# regelschaltplan_e7.net
KiCad netlist of a schematic drawn in EAGLE
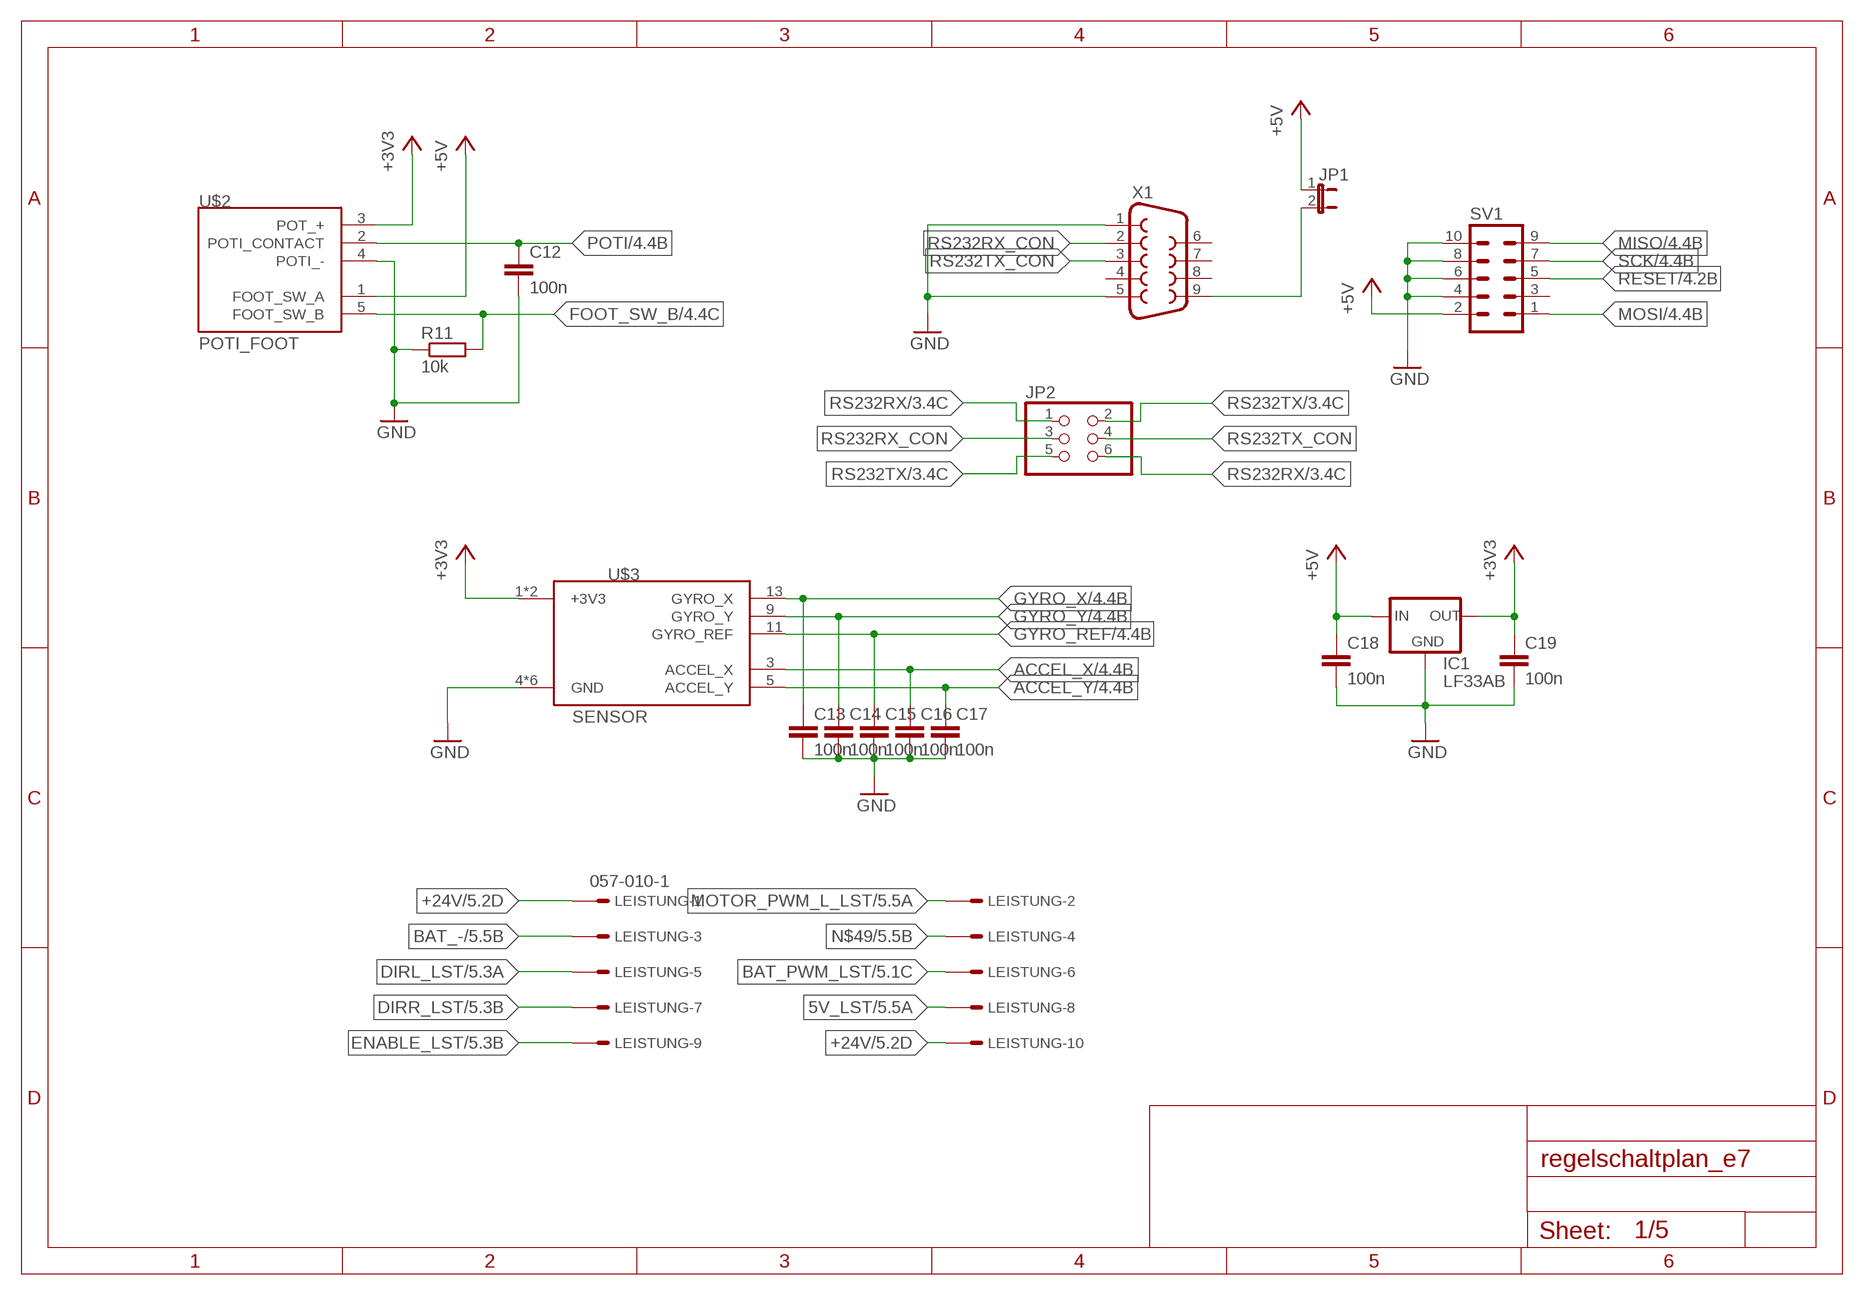
[diagram p0: schematic, sheet 1]
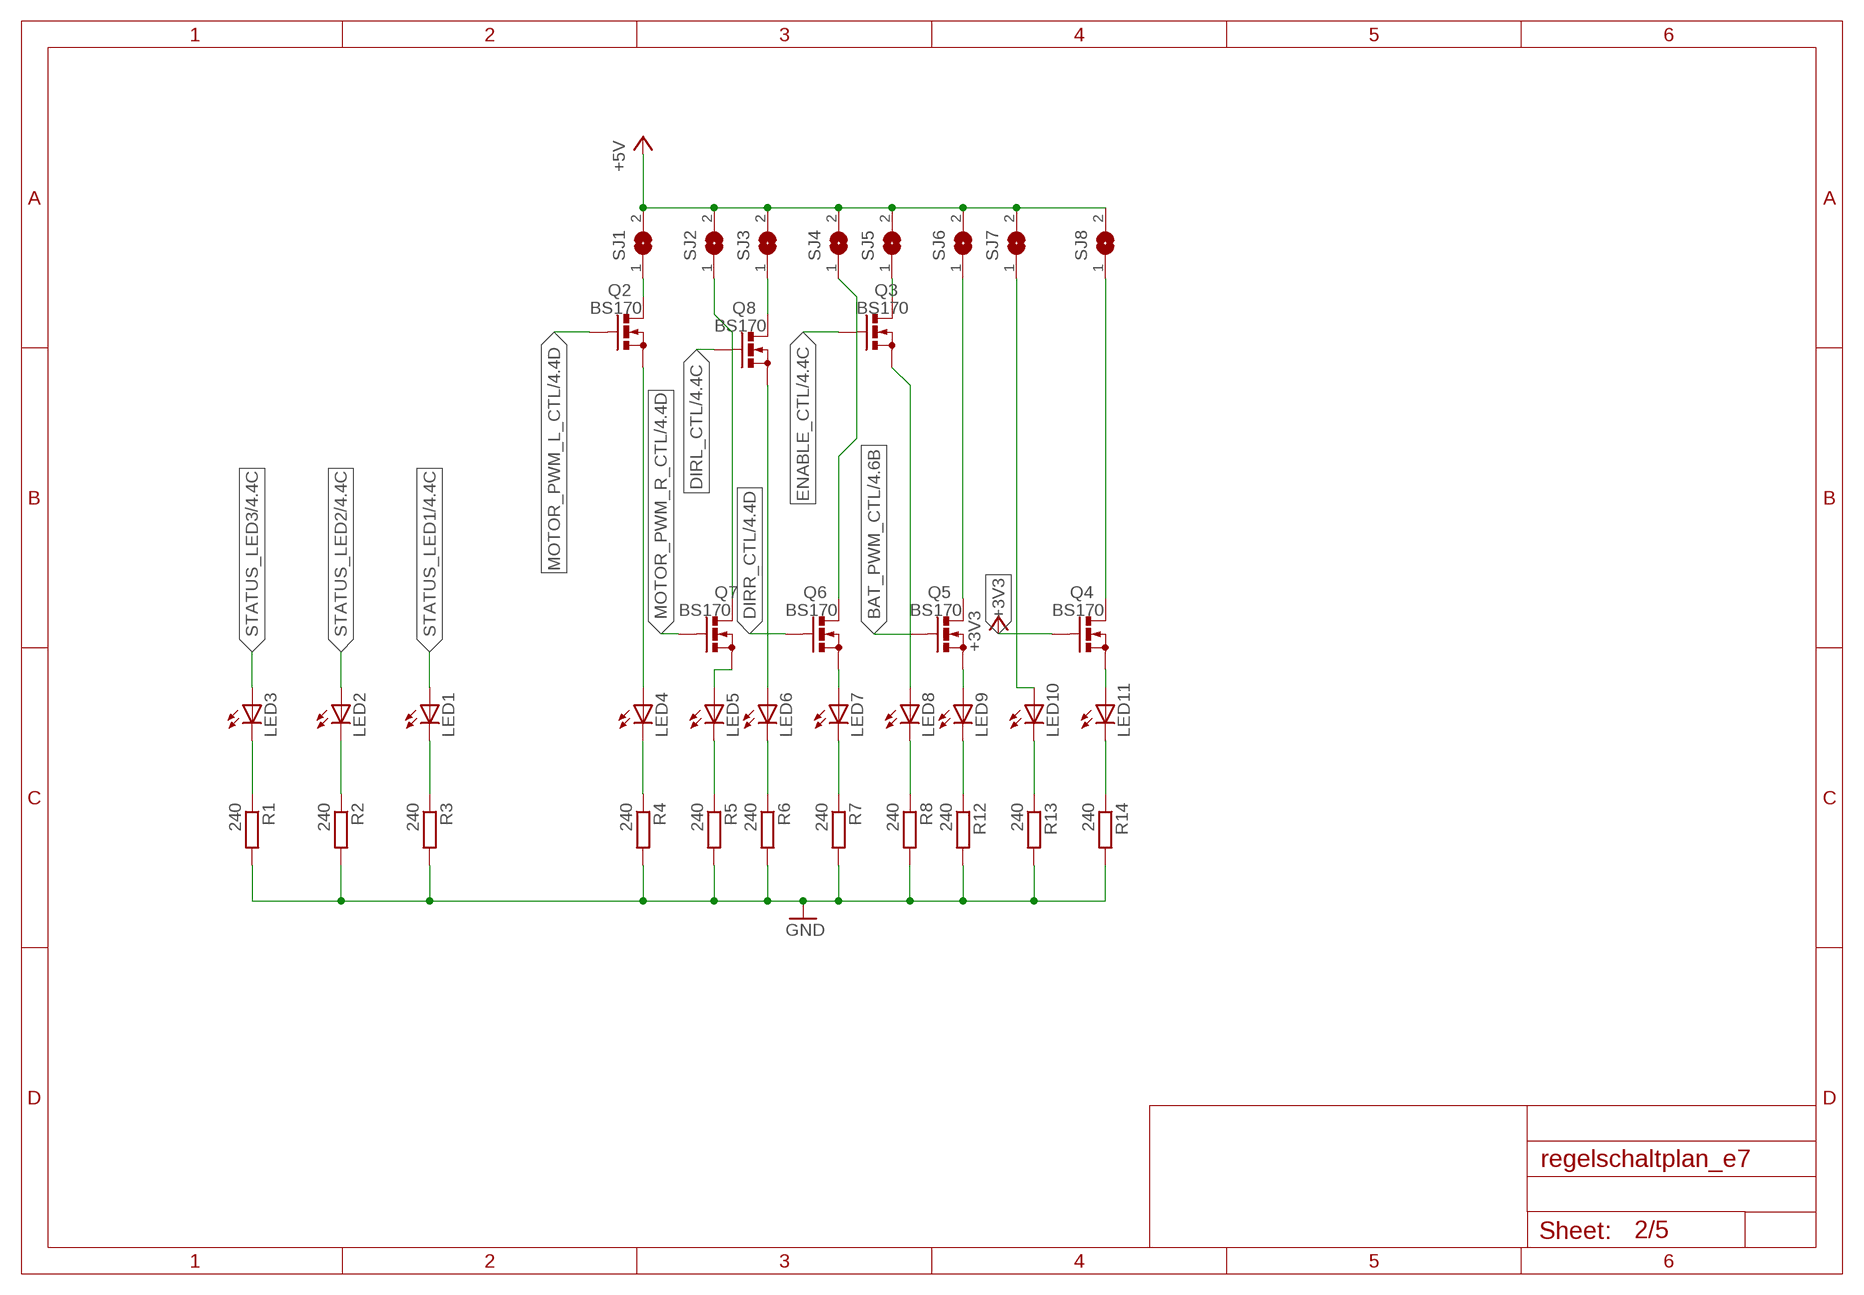
[diagram p1: schematic, sheet 2]
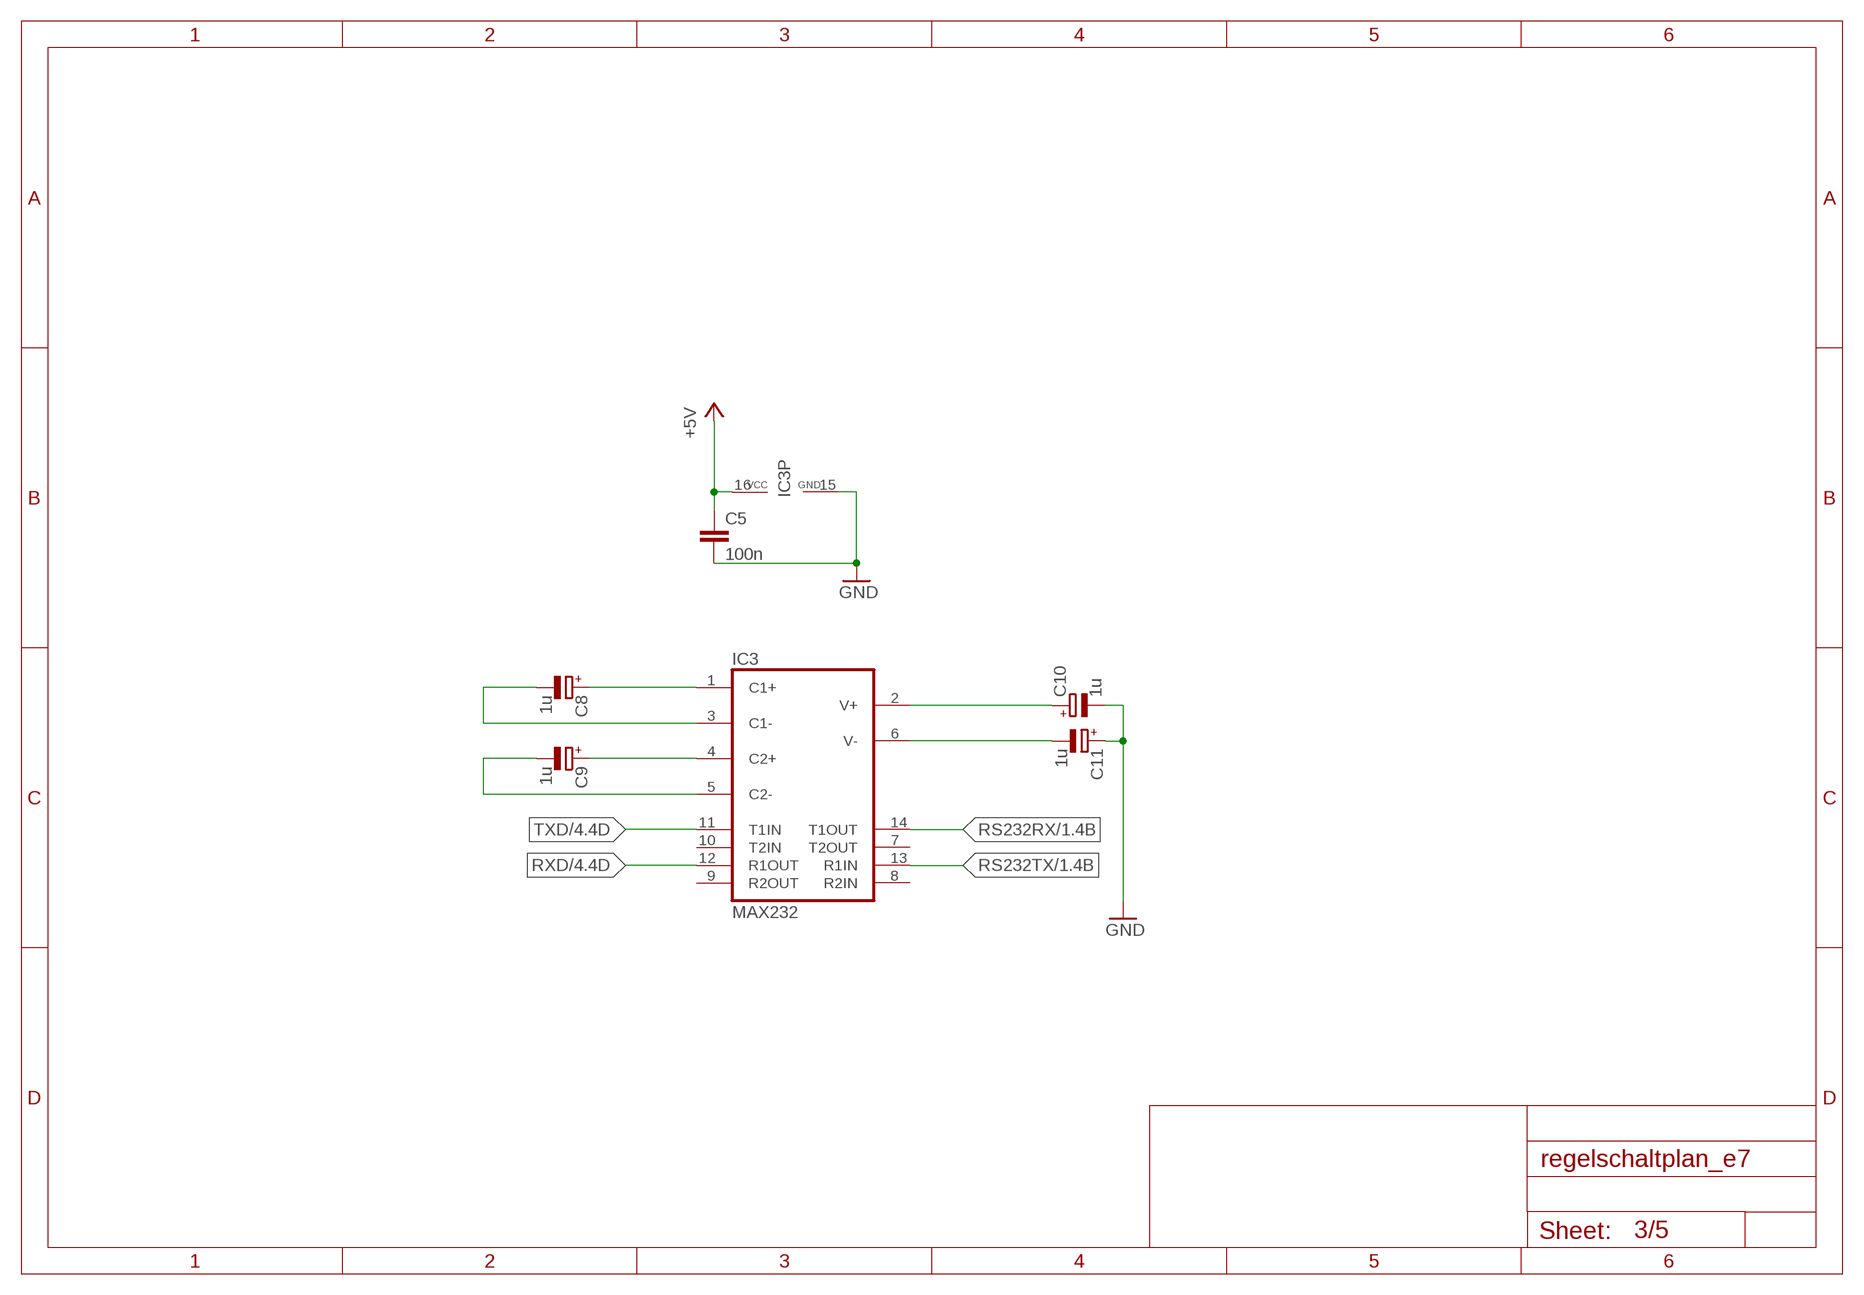
[diagram p2: schematic, sheet 3]
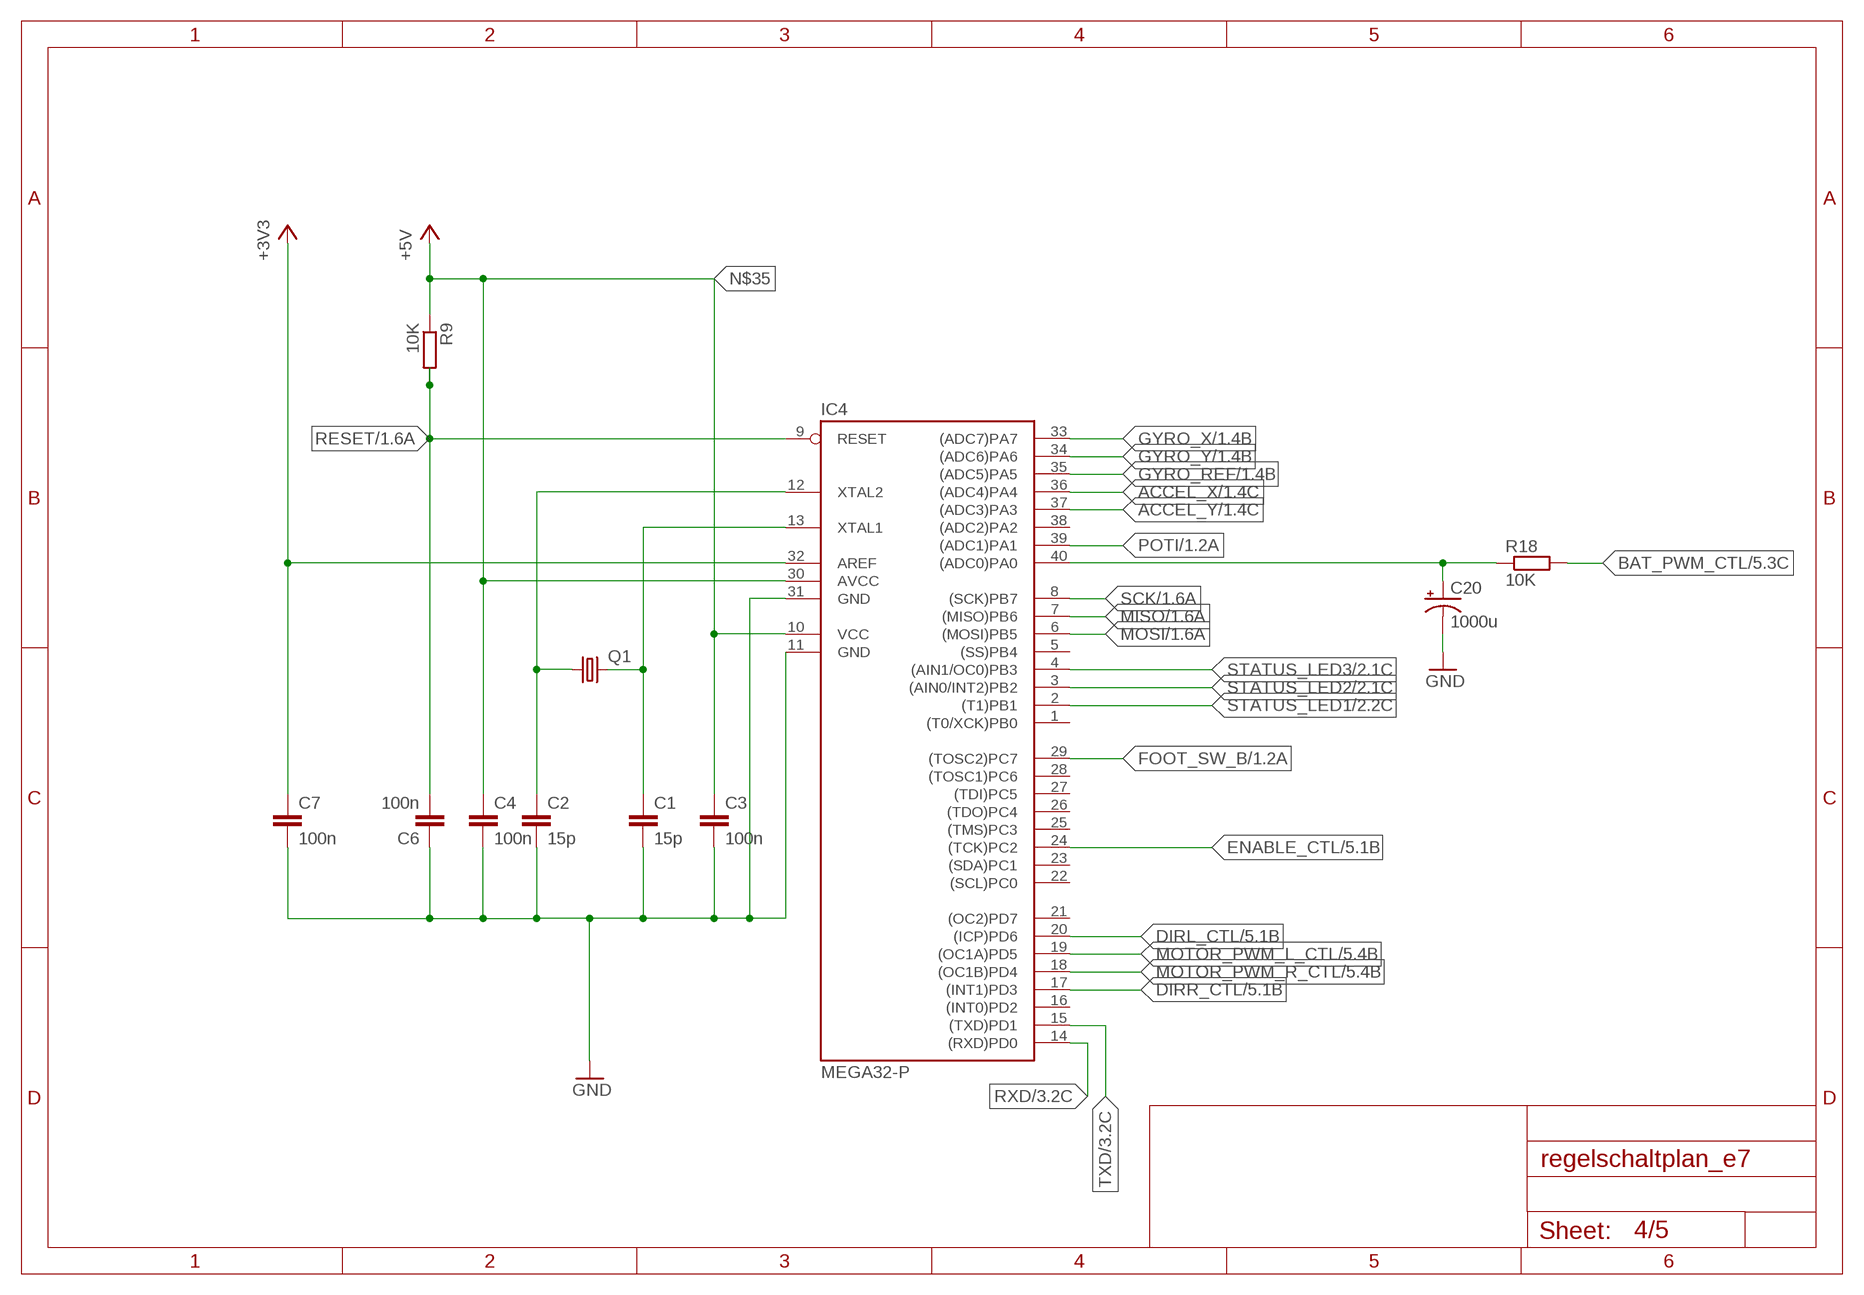
[diagram p3: schematic, sheet 4]
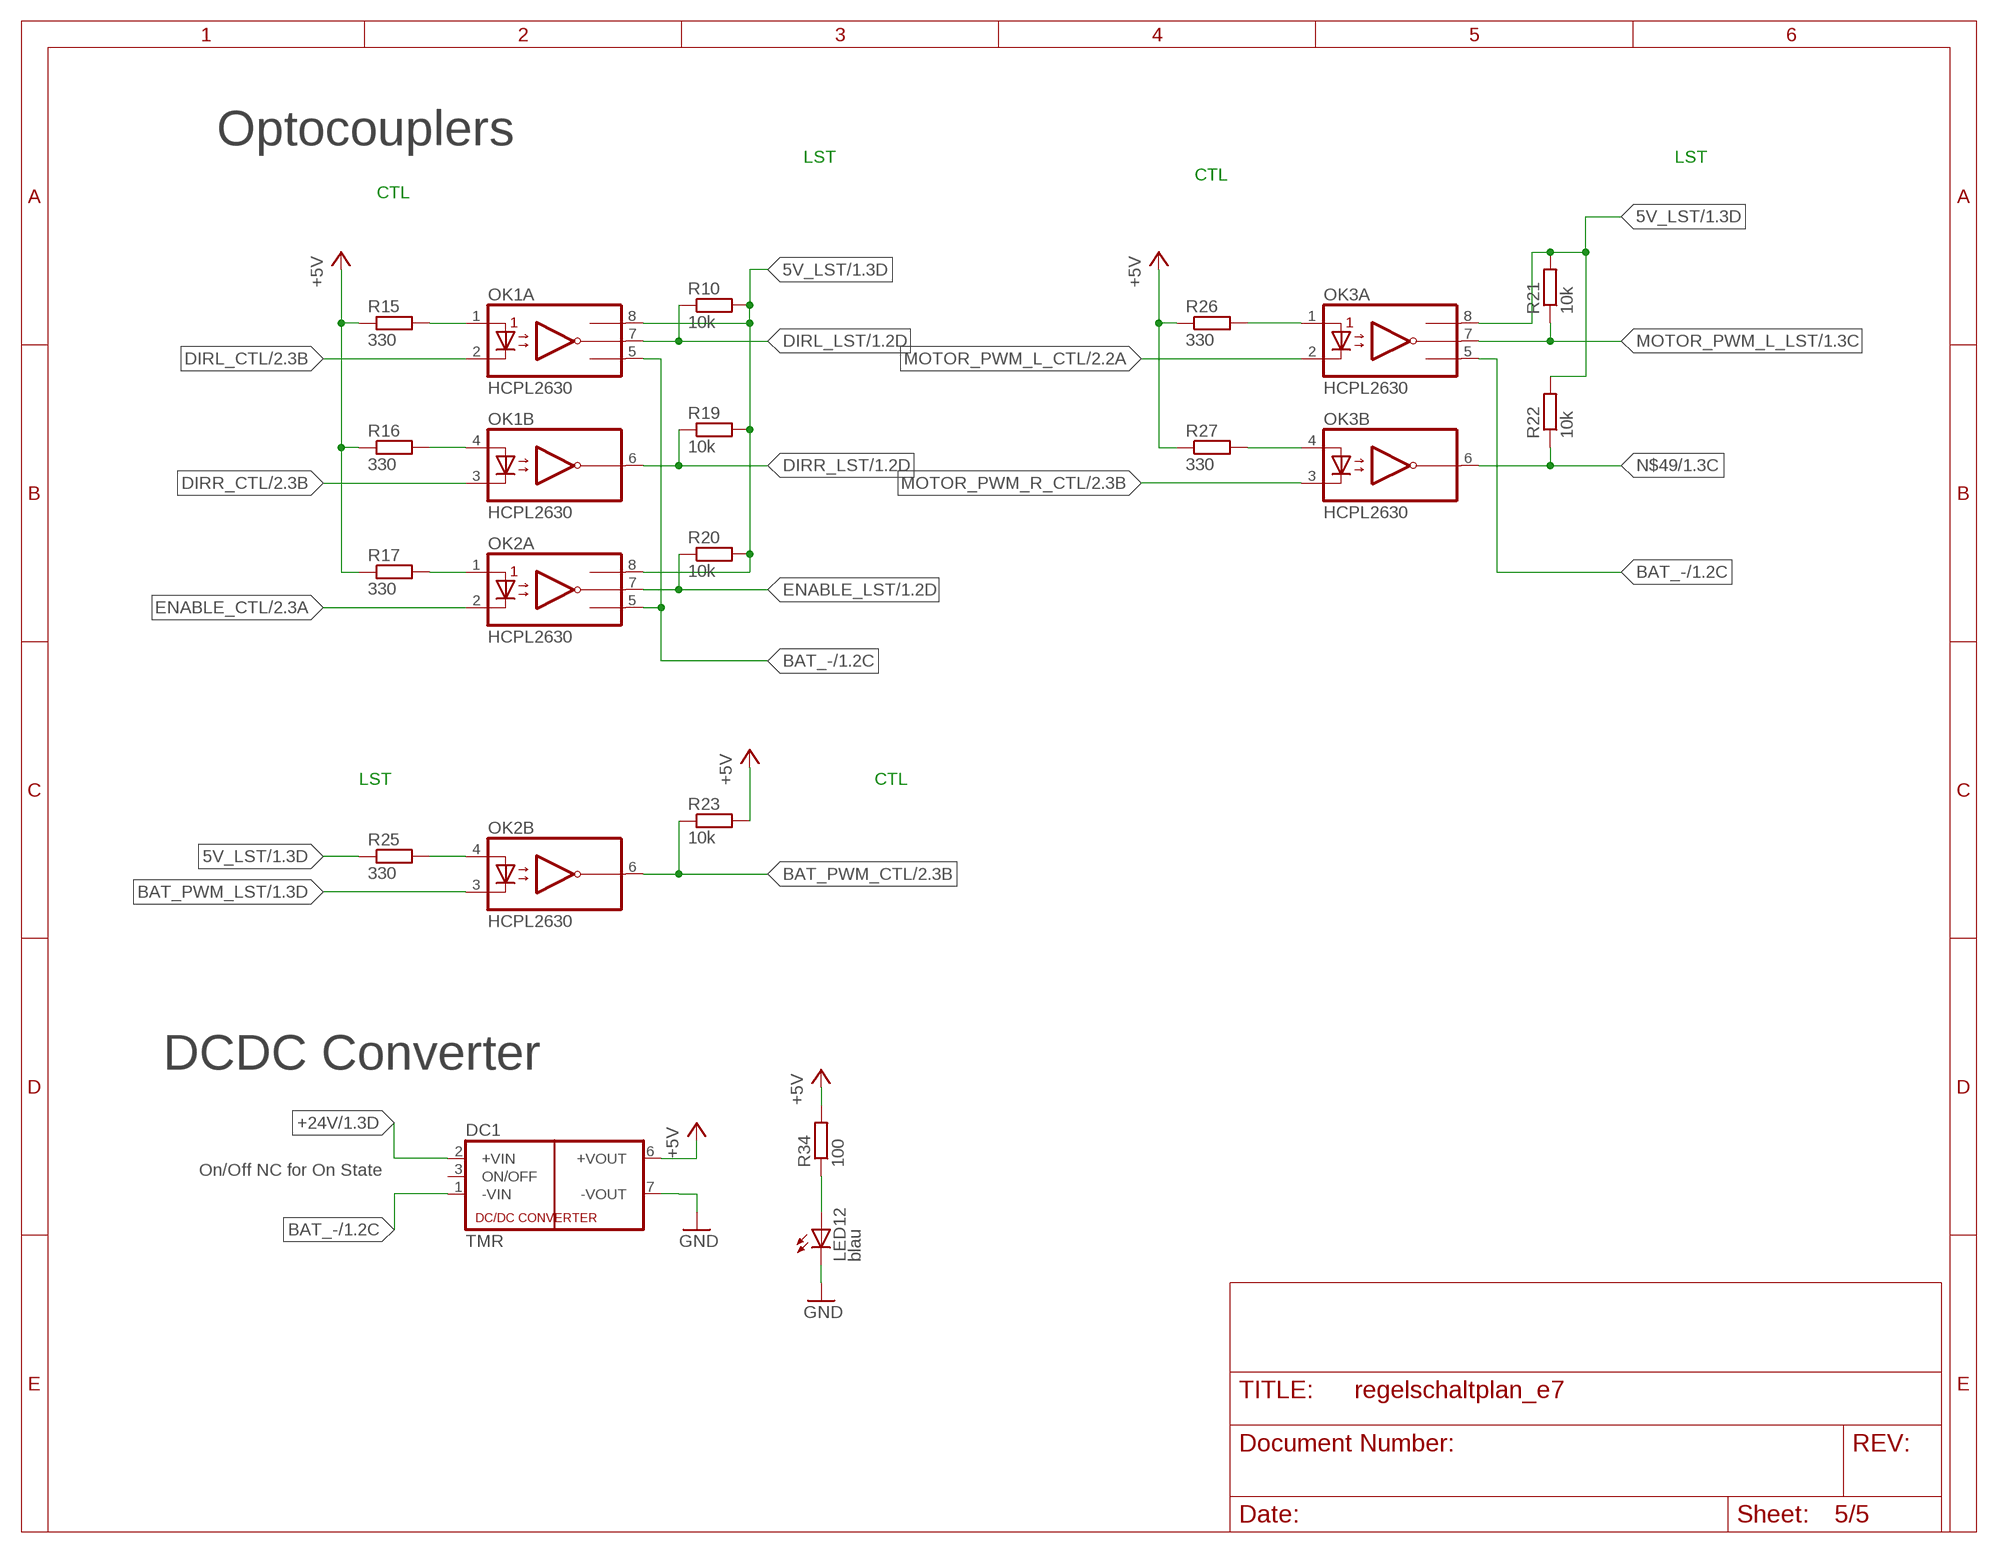
[diagram p4: schematic, sheet 5]

(export (version "E")
  (design (tool "Eeschema 10.0.6"))
  (components
    (comp (ref "C12")
      (value "100n")
      (footprint "eagle-import:C025-025X050")
      (libsource (lib "eagle-import") (part "C-EU025-025X050"))
    )
    (comp (ref "C13")
      (value "100n")
      (footprint "eagle-import:C025-025X050")
      (libsource (lib "eagle-import") (part "C-EU025-025X050"))
    )
    (comp (ref "C14")
      (value "100n")
      (footprint "eagle-import:C025-025X050")
      (libsource (lib "eagle-import") (part "C-EU025-025X050"))
    )
    (comp (ref "C15")
      (value "100n")
      (footprint "eagle-import:C025-025X050")
      (libsource (lib "eagle-import") (part "C-EU025-025X050"))
    )
    (comp (ref "C16")
      (value "100n")
      (footprint "eagle-import:C025-025X050")
      (libsource (lib "eagle-import") (part "C-EU025-025X050"))
    )
    (comp (ref "C17")
      (value "100n")
      (footprint "eagle-import:C025-025X050")
      (libsource (lib "eagle-import") (part "C-EU025-025X050"))
    )
    (comp (ref "C18")
      (value "100n")
      (footprint "eagle-import:C025-025X050")
      (libsource (lib "eagle-import") (part "C-EU025-025X050"))
    )
    (comp (ref "C19")
      (value "100n")
      (footprint "eagle-import:C025-025X050")
      (libsource (lib "eagle-import") (part "C-EU025-025X050"))
    )
    (comp (ref "IC1")
      (value "LF33AB")
      (footprint "eagle-import:TO220")
      (libsource (lib "eagle-import") (part "LF33AB"))
    )
    (comp (ref "JP1")
      (value "JP1E")
      (footprint "eagle-import:JP1")
      (libsource (lib "eagle-import") (part "JP1E"))
    )
    (comp (ref "JP2")
      (value "PINHD-2X3")
      (footprint "eagle-import:2X03")
      (libsource (lib "eagle-import") (part "PINHD-2X3"))
    )
    (comp (ref "LEISTUNG")
      (value "057-010-1")
      (footprint "eagle-import:057-010-1")
      (libsource (lib "eagle-import") (part "057-010-1"))
    )
    (comp (ref "R11")
      (value "10k")
      (footprint "eagle-import:0207_7")
      (libsource (lib "eagle-import") (part "R-EU_0207/7"))
    )
    (comp (ref "SV1")
      (value "MA05-2")
      (footprint "eagle-import:MA05-2")
      (libsource (lib "eagle-import") (part "MA05-2"))
    )
    (comp (ref "U$2")
      (value "POTI_FOOT")
      (footprint "eagle-import:CON_6")
      (libsource (lib "eagle-import") (part "POTI_FOOT"))
    )
    (comp (ref "U$3")
      (value "SENSOR")
      (footprint "eagle-import:CON_14")
      (libsource (lib "eagle-import") (part "SENSOR"))
    )
    (comp (ref "X1")
      (value "F09HP")
      (footprint "eagle-import:F09HP")
      (libsource (lib "eagle-import") (part "F09HP"))
    )
    (comp (ref "DC1")
      (value "TMR")
      (footprint "eagle-import:TRACO_SIP-8")
      (libsource (lib "eagle-import") (part "TMR"))
    )
    (comp (ref "LED12")
      (value "blau")
      (footprint "eagle-import:LED3MM")
      (libsource (lib "eagle-import") (part "LED3MM"))
    )
    (comp (ref "OK1")
      (value "HCPL2630")
      (footprint "eagle-import:DIL08")
      (fields (field (name "MF") "AGILENT TECHNOLOGIES") (field (name "MPN") "HCPL-2630-000E"))
      (libsource (lib "eagle-import") (part "HCPL2630"))
    )
    (comp (ref "OK2")
      (value "HCPL2630")
      (footprint "eagle-import:DIL08")
      (fields (field (name "MF") "AGILENT TECHNOLOGIES") (field (name "MPN") "HCPL-2630-000E"))
      (libsource (lib "eagle-import") (part "HCPL2630"))
    )
    (comp (ref "OK3")
      (value "HCPL2630")
      (footprint "eagle-import:DIL08")
      (fields (field (name "MF") "AGILENT TECHNOLOGIES") (field (name "MPN") "HCPL-2630-000E"))
      (libsource (lib "eagle-import") (part "HCPL2630"))
    )
    (comp (ref "R10")
      (value "10k")
      (footprint "eagle-import:0207_10")
      (libsource (lib "eagle-import") (part "R-EU_0207/10"))
    )
    (comp (ref "R15")
      (value "330")
      (footprint "eagle-import:0207_10")
      (libsource (lib "eagle-import") (part "R-EU_0207/10"))
    )
    (comp (ref "R16")
      (value "330")
      (footprint "eagle-import:0207_10")
      (libsource (lib "eagle-import") (part "R-EU_0207/10"))
    )
    (comp (ref "R17")
      (value "330")
      (footprint "eagle-import:0207_10")
      (libsource (lib "eagle-import") (part "R-EU_0207/10"))
    )
    (comp (ref "R19")
      (value "10k")
      (footprint "eagle-import:0207_10")
      (libsource (lib "eagle-import") (part "R-EU_0207/10"))
    )
    (comp (ref "R20")
      (value "10k")
      (footprint "eagle-import:0207_10")
      (libsource (lib "eagle-import") (part "R-EU_0207/10"))
    )
    (comp (ref "R21")
      (value "10k")
      (footprint "eagle-import:0207_10")
      (libsource (lib "eagle-import") (part "R-EU_0207/10"))
    )
    (comp (ref "R22")
      (value "10k")
      (footprint "eagle-import:0207_10")
      (libsource (lib "eagle-import") (part "R-EU_0207/10"))
    )
    (comp (ref "R23")
      (value "10k")
      (footprint "eagle-import:0207_10")
      (libsource (lib "eagle-import") (part "R-EU_0207/10"))
    )
    (comp (ref "R25")
      (value "330")
      (footprint "eagle-import:0207_10")
      (libsource (lib "eagle-import") (part "R-EU_0207/10"))
    )
    (comp (ref "R26")
      (value "330")
      (footprint "eagle-import:0207_10")
      (libsource (lib "eagle-import") (part "R-EU_0207/10"))
    )
    (comp (ref "R27")
      (value "330")
      (footprint "eagle-import:0207_10")
      (libsource (lib "eagle-import") (part "R-EU_0207/10"))
    )
    (comp (ref "R34")
      (value "100")
      (footprint "eagle-import:0207_10")
      (libsource (lib "eagle-import") (part "R-EU_0207/10"))
    )
    (comp (ref "LED1")
      (value "LED3MM")
      (footprint "eagle-import:LED3MM")
      (libsource (lib "eagle-import") (part "LED3MM"))
    )
    (comp (ref "LED2")
      (value "LED3MM")
      (footprint "eagle-import:LED3MM")
      (libsource (lib "eagle-import") (part "LED3MM"))
    )
    (comp (ref "LED3")
      (value "LED3MM")
      (footprint "eagle-import:LED3MM")
      (libsource (lib "eagle-import") (part "LED3MM"))
    )
    (comp (ref "LED4")
      (value "LED3MM")
      (footprint "eagle-import:LED3MM")
      (libsource (lib "eagle-import") (part "LED3MM"))
    )
    (comp (ref "LED5")
      (value "LED3MM")
      (footprint "eagle-import:LED3MM")
      (libsource (lib "eagle-import") (part "LED3MM"))
    )
    (comp (ref "LED6")
      (value "LED3MM")
      (footprint "eagle-import:LED3MM")
      (libsource (lib "eagle-import") (part "LED3MM"))
    )
    (comp (ref "LED7")
      (value "LED3MM")
      (footprint "eagle-import:LED3MM")
      (libsource (lib "eagle-import") (part "LED3MM"))
    )
    (comp (ref "LED8")
      (value "LED3MM")
      (footprint "eagle-import:LED3MM")
      (libsource (lib "eagle-import") (part "LED3MM"))
    )
    (comp (ref "LED9")
      (value "LED3MM")
      (footprint "eagle-import:LED3MM")
      (libsource (lib "eagle-import") (part "LED3MM"))
    )
    (comp (ref "LED10")
      (value "LED3MM")
      (footprint "eagle-import:LED3MM")
      (libsource (lib "eagle-import") (part "LED3MM"))
    )
    (comp (ref "LED11")
      (value "LED3MM")
      (footprint "eagle-import:LED3MM")
      (libsource (lib "eagle-import") (part "LED3MM"))
    )
    (comp (ref "Q2")
      (value "BS170")
      (footprint "eagle-import:SOT54E")
      (libsource (lib "eagle-import") (part "BS170"))
    )
    (comp (ref "Q3")
      (value "BS170")
      (footprint "eagle-import:SOT54E")
      (libsource (lib "eagle-import") (part "BS170"))
    )
    (comp (ref "Q4")
      (value "BS170")
      (footprint "eagle-import:SOT54E")
      (libsource (lib "eagle-import") (part "BS170"))
    )
    (comp (ref "Q5")
      (value "BS170")
      (footprint "eagle-import:SOT54E")
      (libsource (lib "eagle-import") (part "BS170"))
    )
    (comp (ref "Q6")
      (value "BS170")
      (footprint "eagle-import:SOT54E")
      (libsource (lib "eagle-import") (part "BS170"))
    )
    (comp (ref "Q7")
      (value "BS170")
      (footprint "eagle-import:SOT54E")
      (libsource (lib "eagle-import") (part "BS170"))
    )
    (comp (ref "Q8")
      (value "BS170")
      (footprint "eagle-import:SOT54E")
      (libsource (lib "eagle-import") (part "BS170"))
    )
    (comp (ref "R1")
      (value "240")
      (footprint "eagle-import:0207_7")
      (libsource (lib "eagle-import") (part "R-EU_0207/7"))
    )
    (comp (ref "R2")
      (value "240")
      (footprint "eagle-import:0207_7")
      (libsource (lib "eagle-import") (part "R-EU_0207/7"))
    )
    (comp (ref "R3")
      (value "240")
      (footprint "eagle-import:0207_7")
      (libsource (lib "eagle-import") (part "R-EU_0207/7"))
    )
    (comp (ref "R4")
      (value "240")
      (footprint "eagle-import:0207_7")
      (libsource (lib "eagle-import") (part "R-EU_0207/7"))
    )
    (comp (ref "R5")
      (value "240")
      (footprint "eagle-import:0207_7")
      (libsource (lib "eagle-import") (part "R-EU_0207/7"))
    )
    (comp (ref "R6")
      (value "240")
      (footprint "eagle-import:0207_7")
      (libsource (lib "eagle-import") (part "R-EU_0207/7"))
    )
    (comp (ref "R7")
      (value "240")
      (footprint "eagle-import:0207_7")
      (libsource (lib "eagle-import") (part "R-EU_0207/7"))
    )
    (comp (ref "R8")
      (value "240")
      (footprint "eagle-import:0207_7")
      (libsource (lib "eagle-import") (part "R-EU_0207/7"))
    )
    (comp (ref "R12")
      (value "240")
      (footprint "eagle-import:0207_7")
      (libsource (lib "eagle-import") (part "R-EU_0207/7"))
    )
    (comp (ref "R13")
      (value "240")
      (footprint "eagle-import:0207_7")
      (libsource (lib "eagle-import") (part "R-EU_0207/7"))
    )
    (comp (ref "R14")
      (value "240")
      (footprint "eagle-import:0207_7")
      (libsource (lib "eagle-import") (part "R-EU_0207/7"))
    )
    (comp (ref "SJ1") (value "SJ") (footprint "eagle-import:SJ") (libsource (lib "eagle-import") (part "SJ")))
    (comp (ref "SJ2") (value "SJ") (footprint "eagle-import:SJ") (libsource (lib "eagle-import") (part "SJ")))
    (comp (ref "SJ3") (value "SJ") (footprint "eagle-import:SJ") (libsource (lib "eagle-import") (part "SJ")))
    (comp (ref "SJ4") (value "SJ") (footprint "eagle-import:SJ") (libsource (lib "eagle-import") (part "SJ")))
    (comp (ref "SJ5") (value "SJ") (footprint "eagle-import:SJ") (libsource (lib "eagle-import") (part "SJ")))
    (comp (ref "SJ6") (value "SJ") (footprint "eagle-import:SJ") (libsource (lib "eagle-import") (part "SJ")))
    (comp (ref "SJ7") (value "SJ") (footprint "eagle-import:SJ") (libsource (lib "eagle-import") (part "SJ")))
    (comp (ref "SJ8") (value "SJ") (footprint "eagle-import:SJ") (libsource (lib "eagle-import") (part "SJ")))
    (comp (ref "C1")
      (value "15p")
      (footprint "eagle-import:C025-025X050")
      (libsource (lib "eagle-import") (part "C-EU025-025X050"))
    )
    (comp (ref "C2")
      (value "15p")
      (footprint "eagle-import:C025-025X050")
      (libsource (lib "eagle-import") (part "C-EU025-025X050"))
    )
    (comp (ref "C3")
      (value "100n")
      (footprint "eagle-import:C025-025X050")
      (libsource (lib "eagle-import") (part "C-EU025-025X050"))
    )
    (comp (ref "C4")
      (value "100n")
      (footprint "eagle-import:C025-025X050")
      (libsource (lib "eagle-import") (part "C-EU025-025X050"))
    )
    (comp (ref "C6")
      (value "100n")
      (footprint "eagle-import:C025-025X050")
      (libsource (lib "eagle-import") (part "C-EU025-025X050"))
    )
    (comp (ref "C7")
      (value "100n")
      (footprint "eagle-import:C025-025X050")
      (libsource (lib "eagle-import") (part "C-EU025-025X050"))
    )
    (comp (ref "C20")
      (value "1000u")
      (footprint "eagle-import:E2,5-6E")
      (libsource (lib "eagle-import") (part "CPOL-USE2,5-6E"))
    )
    (comp (ref "IC4")
      (value "MEGA32-P")
      (footprint "eagle-import:DIL40")
      (fields (field (name "MPN") "ATMEGA32-16PU"))
      (libsource (lib "eagle-import") (part "MEGA32-P"))
    )
    (comp (ref "Q1")
      (value "CRYSTALHC49U-V")
      (footprint "eagle-import:HC49U-V")
      (libsource (lib "eagle-import") (part "CRYSTALHC49U-V"))
    )
    (comp (ref "R9")
      (value "10K")
      (footprint "eagle-import:0207_7")
      (libsource (lib "eagle-import") (part "R-EU_0207/7"))
    )
    (comp (ref "R18")
      (value "10K")
      (footprint "eagle-import:0207_7")
      (libsource (lib "eagle-import") (part "R-EU_0207/7"))
    )
    (comp (ref "C5")
      (value "100n")
      (footprint "eagle-import:C025-025X050")
      (libsource (lib "eagle-import") (part "C-EU025-025X050"))
    )
    (comp (ref "C8")
      (value "1u")
      (footprint "eagle-import:E2,5-6E")
      (libsource (lib "eagle-import") (part "CPOL-EUE2,5-6E"))
    )
    (comp (ref "C9")
      (value "1u")
      (footprint "eagle-import:E2,5-6E")
      (libsource (lib "eagle-import") (part "CPOL-EUE2,5-6E"))
    )
    (comp (ref "C10")
      (value "1u")
      (footprint "eagle-import:E2,5-6E")
      (libsource (lib "eagle-import") (part "CPOL-EUE2,5-6E"))
    )
    (comp (ref "C11")
      (value "1u")
      (footprint "eagle-import:E2,5-6E")
      (libsource (lib "eagle-import") (part "CPOL-EUE2,5-6E"))
    )
    (comp (ref "IC3")
      (value "MAX232")
      (footprint "eagle-import:DIL16")
      (fields (field (name "MF") "MAXIM") (field (name "MPN") "MAX232ACPE+"))
      (libsource (lib "eagle-import") (part "MAX232"))
    )
  )
  (nets
    (net (code "1") (name "+3V3") (class "Default")
      (node (ref "C19") (pin "1") (pinfunction "1_1") (pintype "passive"))
      (node (ref "C7") (pin "1") (pinfunction "1_1") (pintype "passive"))
      (node (ref "IC1") (pin "3") (pinfunction "OUT_3") (pintype "passive"))
      (node (ref "IC4") (pin "32") (pinfunction "AREF_32") (pintype "passive"))
      (node (ref "Q4") (pin "G") (pinfunction "G_G") (pintype "passive"))
      (node (ref "U$2") (pin "3") (pinfunction "POT_+_3") (pintype "power_in"))
      (node (ref "U$3") (pin "1") (pinfunction "+3V3_1") (pintype "power_in"))
      (node (ref "U$3") (pin "2") (pinfunction "+3V3_2") (pintype "power_in"))
    )
    (net (code "2") (name "+24V") (class "Default")
      (node (ref "DC1") (pin "2") (pinfunction "+VIN_2") (pintype "passive"))
      (node (ref "LEISTUNG") (pin "1") (pinfunction "S_1") (pintype "passive"))
      (node (ref "LEISTUNG") (pin "10") (pinfunction "S_10") (pintype "passive"))
    )
    (net (code "3") (name "5V_LST") (class "Default")
      (node (ref "LEISTUNG") (pin "8") (pinfunction "S_8") (pintype "passive"))
      (node (ref "OK1") (pin "8") (pinfunction "VCC_8") (pintype "passive"))
      (node (ref "OK2") (pin "8") (pinfunction "VCC_8") (pintype "passive"))
      (node (ref "OK3") (pin "8") (pinfunction "VCC_8") (pintype "passive"))
      (node (ref "R10") (pin "2") (pinfunction "2_2") (pintype "passive"))
      (node (ref "R19") (pin "2") (pinfunction "2_2") (pintype "passive"))
      (node (ref "R20") (pin "2") (pinfunction "2_2") (pintype "passive"))
      (node (ref "R21") (pin "2") (pinfunction "2_2") (pintype "passive"))
      (node (ref "R22") (pin "2") (pinfunction "2_2") (pintype "passive"))
      (node (ref "R25") (pin "1") (pinfunction "1_1") (pintype "passive"))
    )
    (net (code "4") (name "ACCEL_X") (class "Default")
      (node (ref "C16") (pin "1") (pinfunction "1_1") (pintype "passive"))
      (node (ref "IC4") (pin "36") (pinfunction "(ADC4)PA4_36") (pintype "bidirectional"))
      (node (ref "U$3") (pin "3") (pinfunction "ACCEL_X_3") (pintype "output"))
    )
    (net (code "5") (name "ACCEL_Y") (class "Default")
      (node (ref "C17") (pin "1") (pinfunction "1_1") (pintype "passive"))
      (node (ref "IC4") (pin "37") (pinfunction "(ADC3)PA3_37") (pintype "bidirectional"))
      (node (ref "U$3") (pin "5") (pinfunction "ACCEL_Y_5") (pintype "output"))
    )
    (net (code "6") (name "BAT_-") (class "Default")
      (node (ref "DC1") (pin "1") (pinfunction "-VIN_1") (pintype "passive"))
      (node (ref "LEISTUNG") (pin "3") (pinfunction "S_3") (pintype "passive"))
      (node (ref "OK1") (pin "5") (pinfunction "GND_5") (pintype "passive"))
      (node (ref "OK2") (pin "5") (pinfunction "GND_5") (pintype "passive"))
      (node (ref "OK3") (pin "5") (pinfunction "GND_5") (pintype "passive"))
    )
    (net (code "7") (name "BAT_PWM_CTL") (class "Default")
      (node (ref "OK2") (pin "6") (pinfunction "VO2_6") (pintype "passive"))
      (node (ref "Q5") (pin "G") (pinfunction "G_G") (pintype "passive"))
      (node (ref "R18") (pin "2") (pinfunction "2_2") (pintype "passive"))
      (node (ref "R23") (pin "1") (pinfunction "1_1") (pintype "passive"))
    )
    (net (code "8") (name "BAT_PWM_LST") (class "Default")
      (node (ref "LEISTUNG") (pin "6") (pinfunction "S_6") (pintype "passive"))
      (node (ref "OK2") (pin "3") (pinfunction "C2_3") (pintype "passive"))
    )
    (net (code "9") (name "DIRL_CTL") (class "Default")
      (node (ref "IC4") (pin "20") (pinfunction "(ICP)PD6_20") (pintype "bidirectional"))
      (node (ref "OK1") (pin "2") (pinfunction "C1_2") (pintype "passive"))
      (node (ref "Q8") (pin "G") (pinfunction "G_G") (pintype "passive"))
    )
    (net (code "10") (name "DIRL_LST") (class "Default")
      (node (ref "LEISTUNG") (pin "5") (pinfunction "S_5") (pintype "passive"))
      (node (ref "OK1") (pin "7") (pinfunction "VO1_7") (pintype "passive"))
      (node (ref "R10") (pin "1") (pinfunction "1_1") (pintype "passive"))
    )
    (net (code "11") (name "DIRR_CTL") (class "Default")
      (node (ref "IC4") (pin "17") (pinfunction "(INT1)PD3_17") (pintype "bidirectional"))
      (node (ref "OK1") (pin "3") (pinfunction "C2_3") (pintype "passive"))
      (node (ref "Q6") (pin "G") (pinfunction "G_G") (pintype "passive"))
    )
    (net (code "12") (name "DIRR_LST") (class "Default")
      (node (ref "LEISTUNG") (pin "7") (pinfunction "S_7") (pintype "passive"))
      (node (ref "OK1") (pin "6") (pinfunction "VO2_6") (pintype "passive"))
      (node (ref "R19") (pin "1") (pinfunction "1_1") (pintype "passive"))
    )
    (net (code "13") (name "ENABLE_CTL") (class "Default")
      (node (ref "IC4") (pin "24") (pinfunction "(TCK)PC2_24") (pintype "bidirectional"))
      (node (ref "OK2") (pin "2") (pinfunction "C1_2") (pintype "passive"))
      (node (ref "Q3") (pin "G") (pinfunction "G_G") (pintype "passive"))
    )
    (net (code "14") (name "ENABLE_LST") (class "Default")
      (node (ref "LEISTUNG") (pin "9") (pinfunction "S_9") (pintype "passive"))
      (node (ref "OK2") (pin "7") (pinfunction "VO1_7") (pintype "passive"))
      (node (ref "R20") (pin "1") (pinfunction "1_1") (pintype "passive"))
    )
    (net (code "15") (name "FOOT_SW_B") (class "Default")
      (node (ref "IC4") (pin "29") (pinfunction "(TOSC2)PC7_29") (pintype "bidirectional"))
      (node (ref "R11") (pin "2") (pinfunction "2_2") (pintype "passive"))
      (node (ref "U$2") (pin "5") (pinfunction "FOOT_SW_B_5") (pintype "bidirectional"))
    )
    (net (code "16") (name "GND") (class "Default")
      (node (ref "C1") (pin "2") (pinfunction "2_2") (pintype "passive"))
      (node (ref "C10") (pin "-") (pinfunction "-_-") (pintype "passive"))
      (node (ref "C11") (pin "+") (pinfunction "+_+") (pintype "passive"))
      (node (ref "C12") (pin "2") (pinfunction "2_2") (pintype "passive"))
      (node (ref "C13") (pin "2") (pinfunction "2_2") (pintype "passive"))
      (node (ref "C14") (pin "2") (pinfunction "2_2") (pintype "passive"))
      (node (ref "C15") (pin "2") (pinfunction "2_2") (pintype "passive"))
      (node (ref "C16") (pin "2") (pinfunction "2_2") (pintype "passive"))
      (node (ref "C17") (pin "2") (pinfunction "2_2") (pintype "passive"))
      (node (ref "C18") (pin "2") (pinfunction "2_2") (pintype "passive"))
      (node (ref "C19") (pin "2") (pinfunction "2_2") (pintype "passive"))
      (node (ref "C2") (pin "2") (pinfunction "2_2") (pintype "passive"))
      (node (ref "C20") (pin "-") (pinfunction "-_-") (pintype "passive"))
      (node (ref "C3") (pin "2") (pinfunction "2_2") (pintype "passive"))
      (node (ref "C4") (pin "2") (pinfunction "2_2") (pintype "passive"))
      (node (ref "C5") (pin "2") (pinfunction "2_2") (pintype "passive"))
      (node (ref "C6") (pin "1") (pinfunction "1_1") (pintype "passive"))
      (node (ref "C7") (pin "2") (pinfunction "2_2") (pintype "passive"))
      (node (ref "DC1") (pin "7") (pinfunction "-VOUT_7") (pintype "passive"))
      (node (ref "IC1") (pin "2") (pinfunction "GND_2") (pintype "input"))
      (node (ref "IC3") (pin "15") (pinfunction "GND_15") (pintype "power_in"))
      (node (ref "IC4") (pin "11") (pinfunction "GND_11") (pintype "power_in"))
      (node (ref "IC4") (pin "31") (pinfunction "GND_31") (pintype "power_in"))
      (node (ref "LED12") (pin "K") (pinfunction "C_K") (pintype "passive"))
      (node (ref "R1") (pin "2") (pinfunction "2_2") (pintype "passive"))
      (node (ref "R11") (pin "1") (pinfunction "1_1") (pintype "passive"))
      (node (ref "R12") (pin "2") (pinfunction "2_2") (pintype "passive"))
      (node (ref "R13") (pin "2") (pinfunction "2_2") (pintype "passive"))
      (node (ref "R14") (pin "2") (pinfunction "2_2") (pintype "passive"))
      (node (ref "R2") (pin "2") (pinfunction "2_2") (pintype "passive"))
      (node (ref "R3") (pin "2") (pinfunction "2_2") (pintype "passive"))
      (node (ref "R4") (pin "2") (pinfunction "2_2") (pintype "passive"))
      (node (ref "R5") (pin "2") (pinfunction "2_2") (pintype "passive"))
      (node (ref "R6") (pin "2") (pinfunction "2_2") (pintype "passive"))
      (node (ref "R7") (pin "2") (pinfunction "2_2") (pintype "passive"))
      (node (ref "R8") (pin "2") (pinfunction "2_2") (pintype "passive"))
      (node (ref "SV1") (pin "10") (pinfunction "10_10") (pintype "passive"))
      (node (ref "SV1") (pin "4") (pinfunction "4_4") (pintype "passive"))
      (node (ref "SV1") (pin "6") (pinfunction "6_6") (pintype "passive"))
      (node (ref "SV1") (pin "8") (pinfunction "8_8") (pintype "passive"))
      (node (ref "U$2") (pin "4") (pinfunction "POTI_-_4") (pintype "power_in"))
      (node (ref "U$3") (pin "10") (pinfunction "GND_10") (pintype "power_in"))
      (node (ref "U$3") (pin "12") (pinfunction "GND_12") (pintype "power_in"))
      (node (ref "U$3") (pin "14") (pinfunction "GND_14") (pintype "power_in"))
      (node (ref "U$3") (pin "4") (pinfunction "GND_4") (pintype "power_in"))
      (node (ref "U$3") (pin "6") (pinfunction "GND_6") (pintype "power_in"))
      (node (ref "U$3") (pin "8") (pinfunction "GND_8") (pintype "power_in"))
      (node (ref "X1") (pin "1") (pinfunction "1_1") (pintype "passive"))
      (node (ref "X1") (pin "5") (pinfunction "5_5") (pintype "passive"))
    )
    (net (code "17") (name "GYRO_REF") (class "Default")
      (node (ref "C15") (pin "1") (pinfunction "1_1") (pintype "passive"))
      (node (ref "IC4") (pin "35") (pinfunction "(ADC5)PA5_35") (pintype "bidirectional"))
      (node (ref "U$3") (pin "11") (pinfunction "GYRO_REF_11") (pintype "output"))
    )
    (net (code "18") (name "GYRO_X") (class "Default")
      (node (ref "C13") (pin "1") (pinfunction "1_1") (pintype "passive"))
      (node (ref "IC4") (pin "33") (pinfunction "(ADC7)PA7_33") (pintype "bidirectional"))
      (node (ref "U$3") (pin "13") (pinfunction "GYRO_X_13") (pintype "output"))
    )
    (net (code "19") (name "GYRO_Y") (class "Default")
      (node (ref "C14") (pin "1") (pinfunction "1_1") (pintype "passive"))
      (node (ref "IC4") (pin "34") (pinfunction "(ADC6)PA6_34") (pintype "bidirectional"))
      (node (ref "U$3") (pin "9") (pinfunction "GYRO_Y_9") (pintype "output"))
    )
    (net (code "20") (name "MISO") (class "Default")
      (node (ref "IC4") (pin "7") (pinfunction "(MISO)PB6_7") (pintype "bidirectional"))
      (node (ref "SV1") (pin "9") (pinfunction "9_9") (pintype "passive"))
    )
    (net (code "21") (name "MOSI") (class "Default")
      (node (ref "IC4") (pin "6") (pinfunction "(MOSI)PB5_6") (pintype "bidirectional"))
      (node (ref "SV1") (pin "1") (pinfunction "1_1") (pintype "passive"))
    )
    (net (code "22") (name "MOTOR_PWM_L_CTL") (class "Default")
      (node (ref "IC4") (pin "19") (pinfunction "(OC1A)PD5_19") (pintype "bidirectional"))
      (node (ref "OK3") (pin "2") (pinfunction "C1_2") (pintype "passive"))
      (node (ref "Q2") (pin "G") (pinfunction "G_G") (pintype "passive"))
    )
    (net (code "23") (name "MOTOR_PWM_L_LST") (class "Default")
      (node (ref "LEISTUNG") (pin "2") (pinfunction "S_2") (pintype "passive"))
      (node (ref "OK3") (pin "7") (pinfunction "VO1_7") (pintype "passive"))
      (node (ref "R21") (pin "1") (pinfunction "1_1") (pintype "passive"))
    )
    (net (code "24") (name "MOTOR_PWM_R_CTL") (class "Default")
      (node (ref "IC4") (pin "18") (pinfunction "(OC1B)PD4_18") (pintype "bidirectional"))
      (node (ref "OK3") (pin "3") (pinfunction "C2_3") (pintype "passive"))
      (node (ref "Q7") (pin "G") (pinfunction "G_G") (pintype "passive"))
    )
    (net (code "25") (name "N$35") (class "Default")
      (node (ref "C18") (pin "1") (pinfunction "1_1") (pintype "passive"))
      (node (ref "C3") (pin "1") (pinfunction "1_1") (pintype "passive"))
      (node (ref "C4") (pin "1") (pinfunction "1_1") (pintype "passive"))
      (node (ref "C5") (pin "1") (pinfunction "1_1") (pintype "passive"))
      (node (ref "DC1") (pin "6") (pinfunction "+VOUT_6") (pintype "passive"))
      (node (ref "IC1") (pin "1") (pinfunction "IN_1") (pintype "input"))
      (node (ref "IC3") (pin "16") (pinfunction "VCC_16") (pintype "power_in"))
      (node (ref "IC4") (pin "10") (pinfunction "VCC_10") (pintype "power_in"))
      (node (ref "IC4") (pin "30") (pinfunction "AVCC_30") (pintype "power_in"))
      (node (ref "JP1") (pin "1") (pinfunction "1_1") (pintype "passive"))
      (node (ref "R15") (pin "1") (pinfunction "1_1") (pintype "passive"))
      (node (ref "R16") (pin "1") (pinfunction "1_1") (pintype "passive"))
      (node (ref "R17") (pin "1") (pinfunction "1_1") (pintype "passive"))
      (node (ref "R23") (pin "2") (pinfunction "2_2") (pintype "passive"))
      (node (ref "R26") (pin "1") (pinfunction "1_1") (pintype "passive"))
      (node (ref "R27") (pin "1") (pinfunction "1_1") (pintype "passive"))
      (node (ref "R34") (pin "2") (pinfunction "2_2") (pintype "passive"))
      (node (ref "R9") (pin "1") (pinfunction "1_1") (pintype "passive"))
      (node (ref "SJ1") (pin "2") (pinfunction "2_2") (pintype "passive"))
      (node (ref "SJ2") (pin "2") (pinfunction "2_2") (pintype "passive"))
      (node (ref "SJ3") (pin "2") (pinfunction "2_2") (pintype "passive"))
      (node (ref "SJ4") (pin "2") (pinfunction "2_2") (pintype "passive"))
      (node (ref "SJ5") (pin "2") (pinfunction "2_2") (pintype "passive"))
      (node (ref "SJ6") (pin "2") (pinfunction "2_2") (pintype "passive"))
      (node (ref "SJ7") (pin "2") (pinfunction "2_2") (pintype "passive"))
      (node (ref "SJ8") (pin "2") (pinfunction "2_2") (pintype "passive"))
      (node (ref "SV1") (pin "2") (pinfunction "2_2") (pintype "passive"))
      (node (ref "U$2") (pin "1") (pinfunction "FOOT_SW_A_1") (pintype "bidirectional"))
    )
    (net (code "26") (name "N$49") (class "Default")
      (node (ref "LEISTUNG") (pin "4") (pinfunction "S_4") (pintype "passive"))
      (node (ref "OK3") (pin "6") (pinfunction "VO2_6") (pintype "passive"))
      (node (ref "R22") (pin "1") (pinfunction "1_1") (pintype "passive"))
    )
    (net (code "27") (name "Net-(IC3A-C1+)") (class "Default")
      (node (ref "C8") (pin "+") (pinfunction "+_+") (pintype "passive"))
      (node (ref "IC3") (pin "1") (pinfunction "C1+_1") (pintype "bidirectional"))
    )
    (net (code "28") (name "Net-(IC3A-C1-)") (class "Default")
      (node (ref "C8") (pin "-") (pinfunction "-_-") (pintype "passive"))
      (node (ref "IC3") (pin "3") (pinfunction "C1-_3") (pintype "bidirectional"))
    )
    (net (code "29") (name "Net-(IC3A-C2+)") (class "Default")
      (node (ref "C9") (pin "+") (pinfunction "+_+") (pintype "passive"))
      (node (ref "IC3") (pin "4") (pinfunction "C2+_4") (pintype "bidirectional"))
    )
    (net (code "30") (name "Net-(IC3A-C2-)") (class "Default")
      (node (ref "C9") (pin "-") (pinfunction "-_-") (pintype "passive"))
      (node (ref "IC3") (pin "5") (pinfunction "C2-_5") (pintype "bidirectional"))
    )
    (net (code "31") (name "Net-(IC3A-V+)") (class "Default")
      (node (ref "C10") (pin "+") (pinfunction "+_+") (pintype "passive"))
      (node (ref "IC3") (pin "2") (pinfunction "V+_2") (pintype "bidirectional"))
    )
    (net (code "32") (name "Net-(IC3A-V-)") (class "Default")
      (node (ref "C11") (pin "-") (pinfunction "-_-") (pintype "passive"))
      (node (ref "IC3") (pin "6") (pinfunction "V-_6") (pintype "bidirectional"))
    )
    (net (code "33") (name "Net-(IC4-(ADC0)PA0)") (class "Default")
      (node (ref "C20") (pin "+") (pinfunction "+_+") (pintype "passive"))
      (node (ref "IC4") (pin "40") (pinfunction "(ADC0)PA0_40") (pintype "bidirectional"))
      (node (ref "R18") (pin "1") (pinfunction "1_1") (pintype "passive"))
    )
    (net (code "34") (name "Net-(IC4-XTAL1)") (class "Default")
      (node (ref "C1") (pin "1") (pinfunction "1_1") (pintype "passive"))
      (node (ref "IC4") (pin "13") (pinfunction "XTAL1_13") (pintype "bidirectional"))
      (node (ref "Q1") (pin "2") (pinfunction "2_2") (pintype "passive"))
    )
    (net (code "35") (name "Net-(IC4-XTAL2)") (class "Default")
      (node (ref "C2") (pin "1") (pinfunction "1_1") (pintype "passive"))
      (node (ref "IC4") (pin "12") (pinfunction "XTAL2_12") (pintype "bidirectional"))
      (node (ref "Q1") (pin "1") (pinfunction "1_1") (pintype "passive"))
    )
    (net (code "36") (name "Net-(JP1-Pad2)") (class "Default")
      (node (ref "JP1") (pin "2") (pinfunction "2_2") (pintype "passive"))
      (node (ref "X1") (pin "9") (pinfunction "9_9") (pintype "passive"))
    )
    (net (code "37") (name "Net-(LED1-C)") (class "Default")
      (node (ref "LED1") (pin "K") (pinfunction "C_K") (pintype "passive"))
      (node (ref "R3") (pin "1") (pinfunction "1_1") (pintype "passive"))
    )
    (net (code "38") (name "Net-(LED2-C)") (class "Default")
      (node (ref "LED2") (pin "K") (pinfunction "C_K") (pintype "passive"))
      (node (ref "R2") (pin "1") (pinfunction "1_1") (pintype "passive"))
    )
    (net (code "39") (name "Net-(LED3-C)") (class "Default")
      (node (ref "LED3") (pin "K") (pinfunction "C_K") (pintype "passive"))
      (node (ref "R1") (pin "1") (pinfunction "1_1") (pintype "passive"))
    )
    (net (code "40") (name "Net-(LED4-C)") (class "Default")
      (node (ref "LED4") (pin "K") (pinfunction "C_K") (pintype "passive"))
      (node (ref "R4") (pin "1") (pinfunction "1_1") (pintype "passive"))
    )
    (net (code "41") (name "Net-(LED4-PadA)") (class "Default")
      (node (ref "LED4") (pin "A") (pinfunction "A_A") (pintype "passive"))
      (node (ref "Q2") (pin "S") (pinfunction "S_S") (pintype "passive"))
    )
    (net (code "42") (name "Net-(LED5-C)") (class "Default")
      (node (ref "LED5") (pin "K") (pinfunction "C_K") (pintype "passive"))
      (node (ref "R5") (pin "1") (pinfunction "1_1") (pintype "passive"))
    )
    (net (code "43") (name "Net-(LED5-PadA)") (class "Default")
      (node (ref "LED5") (pin "A") (pinfunction "A_A") (pintype "passive"))
      (node (ref "Q7") (pin "S") (pinfunction "S_S") (pintype "passive"))
    )
    (net (code "44") (name "Net-(LED6-C)") (class "Default")
      (node (ref "LED6") (pin "K") (pinfunction "C_K") (pintype "passive"))
      (node (ref "R6") (pin "1") (pinfunction "1_1") (pintype "passive"))
    )
    (net (code "45") (name "Net-(LED6-PadA)") (class "Default")
      (node (ref "LED6") (pin "A") (pinfunction "A_A") (pintype "passive"))
      (node (ref "Q8") (pin "S") (pinfunction "S_S") (pintype "passive"))
    )
    (net (code "46") (name "Net-(LED7-C)") (class "Default")
      (node (ref "LED7") (pin "K") (pinfunction "C_K") (pintype "passive"))
      (node (ref "R7") (pin "1") (pinfunction "1_1") (pintype "passive"))
    )
    (net (code "47") (name "Net-(LED7-PadA)") (class "Default")
      (node (ref "LED7") (pin "A") (pinfunction "A_A") (pintype "passive"))
      (node (ref "Q6") (pin "S") (pinfunction "S_S") (pintype "passive"))
    )
    (net (code "48") (name "Net-(LED8-C)") (class "Default")
      (node (ref "LED8") (pin "K") (pinfunction "C_K") (pintype "passive"))
      (node (ref "R8") (pin "1") (pinfunction "1_1") (pintype "passive"))
    )
    (net (code "49") (name "Net-(LED8-PadA)") (class "Default")
      (node (ref "LED8") (pin "A") (pinfunction "A_A") (pintype "passive"))
      (node (ref "Q3") (pin "S") (pinfunction "S_S") (pintype "passive"))
    )
    (net (code "50") (name "Net-(LED9-C)") (class "Default")
      (node (ref "LED9") (pin "K") (pinfunction "C_K") (pintype "passive"))
      (node (ref "R12") (pin "1") (pinfunction "1_1") (pintype "passive"))
    )
    (net (code "51") (name "Net-(LED9-PadA)") (class "Default")
      (node (ref "LED9") (pin "A") (pinfunction "A_A") (pintype "passive"))
      (node (ref "Q5") (pin "S") (pinfunction "S_S") (pintype "passive"))
    )
    (net (code "52") (name "Net-(LED10-C)") (class "Default")
      (node (ref "LED10") (pin "K") (pinfunction "C_K") (pintype "passive"))
      (node (ref "R13") (pin "1") (pinfunction "1_1") (pintype "passive"))
    )
    (net (code "53") (name "Net-(LED10-PadA)") (class "Default")
      (node (ref "LED10") (pin "A") (pinfunction "A_A") (pintype "passive"))
      (node (ref "SJ7") (pin "1") (pinfunction "1_1") (pintype "passive"))
    )
    (net (code "54") (name "Net-(LED11-C)") (class "Default")
      (node (ref "LED11") (pin "K") (pinfunction "C_K") (pintype "passive"))
      (node (ref "R14") (pin "1") (pinfunction "1_1") (pintype "passive"))
    )
    (net (code "55") (name "Net-(LED11-PadA)") (class "Default")
      (node (ref "LED11") (pin "A") (pinfunction "A_A") (pintype "passive"))
      (node (ref "Q4") (pin "S") (pinfunction "S_S") (pintype "passive"))
    )
    (net (code "56") (name "Net-(LED12-PadA)") (class "Default")
      (node (ref "LED12") (pin "A") (pinfunction "A_A") (pintype "passive"))
      (node (ref "R34") (pin "1") (pinfunction "1_1") (pintype "passive"))
    )
    (net (code "57") (name "Net-(OK1A-A1)") (class "Default")
      (node (ref "OK1") (pin "1") (pinfunction "A1_1") (pintype "passive"))
      (node (ref "R15") (pin "2") (pinfunction "2_2") (pintype "passive"))
    )
    (net (code "58") (name "Net-(OK1B-A2)") (class "Default")
      (node (ref "OK1") (pin "4") (pinfunction "A2_4") (pintype "passive"))
      (node (ref "R16") (pin "2") (pinfunction "2_2") (pintype "passive"))
    )
    (net (code "59") (name "Net-(OK2A-A1)") (class "Default")
      (node (ref "OK2") (pin "1") (pinfunction "A1_1") (pintype "passive"))
      (node (ref "R17") (pin "2") (pinfunction "2_2") (pintype "passive"))
    )
    (net (code "60") (name "Net-(OK2B-A2)") (class "Default")
      (node (ref "OK2") (pin "4") (pinfunction "A2_4") (pintype "passive"))
      (node (ref "R25") (pin "2") (pinfunction "2_2") (pintype "passive"))
    )
    (net (code "61") (name "Net-(OK3A-A1)") (class "Default")
      (node (ref "OK3") (pin "1") (pinfunction "A1_1") (pintype "passive"))
      (node (ref "R26") (pin "2") (pinfunction "2_2") (pintype "passive"))
    )
    (net (code "62") (name "Net-(OK3B-A2)") (class "Default")
      (node (ref "OK3") (pin "4") (pinfunction "A2_4") (pintype "passive"))
      (node (ref "R27") (pin "2") (pinfunction "2_2") (pintype "passive"))
    )
    (net (code "63") (name "Net-(Q2-PadD)") (class "Default")
      (node (ref "Q2") (pin "D") (pinfunction "D_D") (pintype "passive"))
      (node (ref "SJ1") (pin "1") (pinfunction "1_1") (pintype "passive"))
    )
    (net (code "64") (name "Net-(Q3-PadD)") (class "Default")
      (node (ref "Q3") (pin "D") (pinfunction "D_D") (pintype "passive"))
      (node (ref "SJ5") (pin "1") (pinfunction "1_1") (pintype "passive"))
    )
    (net (code "65") (name "Net-(Q4-PadD)") (class "Default")
      (node (ref "Q4") (pin "D") (pinfunction "D_D") (pintype "passive"))
      (node (ref "SJ8") (pin "1") (pinfunction "1_1") (pintype "passive"))
    )
    (net (code "66") (name "Net-(Q5-PadD)") (class "Default")
      (node (ref "Q5") (pin "D") (pinfunction "D_D") (pintype "passive"))
      (node (ref "SJ6") (pin "1") (pinfunction "1_1") (pintype "passive"))
    )
    (net (code "67") (name "Net-(Q6-PadD)") (class "Default")
      (node (ref "Q6") (pin "D") (pinfunction "D_D") (pintype "passive"))
      (node (ref "SJ4") (pin "1") (pinfunction "1_1") (pintype "passive"))
    )
    (net (code "68") (name "Net-(Q7-PadD)") (class "Default")
      (node (ref "Q7") (pin "D") (pinfunction "D_D") (pintype "passive"))
      (node (ref "SJ2") (pin "1") (pinfunction "1_1") (pintype "passive"))
    )
    (net (code "69") (name "Net-(Q8-PadD)") (class "Default")
      (node (ref "Q8") (pin "D") (pinfunction "D_D") (pintype "passive"))
      (node (ref "SJ3") (pin "1") (pinfunction "1_1") (pintype "passive"))
    )
    (net (code "70") (name "POTI") (class "Default")
      (node (ref "C12") (pin "1") (pinfunction "1_1") (pintype "passive"))
      (node (ref "IC4") (pin "39") (pinfunction "(ADC1)PA1_39") (pintype "bidirectional"))
      (node (ref "U$2") (pin "2") (pinfunction "POTI_CONTACT_2") (pintype "output"))
    )
    (net (code "71") (name "RESET") (class "Default")
      (node (ref "C6") (pin "2") (pinfunction "2_2") (pintype "passive"))
      (node (ref "IC4") (pin "9") (pinfunction "RESET_9") (pintype "input"))
      (node (ref "R9") (pin "2") (pinfunction "2_2") (pintype "passive"))
      (node (ref "SV1") (pin "5") (pinfunction "5_5") (pintype "passive"))
    )
    (net (code "72") (name "RS232RX") (class "Default")
      (node (ref "IC3") (pin "14") (pinfunction "T1OUT_14") (pintype "output"))
      (node (ref "JP2") (pin "1") (pinfunction "1_1") (pintype "passive"))
      (node (ref "JP2") (pin "6") (pinfunction "6_6") (pintype "passive"))
    )
    (net (code "73") (name "RS232RX_CON") (class "Default")
      (node (ref "JP2") (pin "3") (pinfunction "3_3") (pintype "passive"))
      (node (ref "X1") (pin "2") (pinfunction "2_2") (pintype "passive"))
    )
    (net (code "74") (name "RS232TX") (class "Default")
      (node (ref "IC3") (pin "13") (pinfunction "R1IN_13") (pintype "input"))
      (node (ref "JP2") (pin "2") (pinfunction "2_2") (pintype "passive"))
      (node (ref "JP2") (pin "5") (pinfunction "5_5") (pintype "passive"))
    )
    (net (code "75") (name "RS232TX_CON") (class "Default")
      (node (ref "JP2") (pin "4") (pinfunction "4_4") (pintype "passive"))
      (node (ref "X1") (pin "3") (pinfunction "3_3") (pintype "passive"))
    )
    (net (code "76") (name "RXD") (class "Default")
      (node (ref "IC3") (pin "12") (pinfunction "R1OUT_12") (pintype "output"))
      (node (ref "IC4") (pin "14") (pinfunction "(RXD)PD0_14") (pintype "bidirectional"))
    )
    (net (code "77") (name "SCK") (class "Default")
      (node (ref "IC4") (pin "8") (pinfunction "(SCK)PB7_8") (pintype "bidirectional"))
      (node (ref "SV1") (pin "7") (pinfunction "7_7") (pintype "passive"))
    )
    (net (code "78") (name "STATUS_LED1") (class "Default")
      (node (ref "IC4") (pin "2") (pinfunction "(T1)PB1_2") (pintype "bidirectional"))
      (node (ref "LED1") (pin "A") (pinfunction "A_A") (pintype "passive"))
    )
    (net (code "79") (name "STATUS_LED2") (class "Default")
      (node (ref "IC4") (pin "3") (pinfunction "(AIN0/INT2)PB2_3") (pintype "bidirectional"))
      (node (ref "LED2") (pin "A") (pinfunction "A_A") (pintype "passive"))
    )
    (net (code "80") (name "STATUS_LED3") (class "Default")
      (node (ref "IC4") (pin "4") (pinfunction "(AIN1/OC0)PB3_4") (pintype "bidirectional"))
      (node (ref "LED3") (pin "A") (pinfunction "A_A") (pintype "passive"))
    )
    (net (code "81") (name "TXD") (class "Default")
      (node (ref "IC3") (pin "11") (pinfunction "T1IN_11") (pintype "input"))
      (node (ref "IC4") (pin "15") (pinfunction "(TXD)PD1_15") (pintype "bidirectional"))
    )
    (net (code "82") (name "unconnected-(DC1-ON{slash}OFF-Pad3)") (class "Default")
      (node (ref "DC1") (pin "3") (pinfunction "ON/OFF_3") (pintype "passive"))
    )
    (net (code "83") (name "unconnected-(IC3A-R2IN-Pad8)") (class "Default")
      (node (ref "IC3") (pin "8") (pinfunction "R2IN_8") (pintype "input"))
    )
    (net (code "84") (name "unconnected-(IC3A-R2OUT-Pad9)") (class "Default")
      (node (ref "IC3") (pin "9") (pinfunction "R2OUT_9") (pintype "output"))
    )
    (net (code "85") (name "unconnected-(IC3A-T2IN-Pad10)") (class "Default")
      (node (ref "IC3") (pin "10") (pinfunction "T2IN_10") (pintype "input"))
    )
    (net (code "86") (name "unconnected-(IC3A-T2OUT-Pad7)") (class "Default")
      (node (ref "IC3") (pin "7") (pinfunction "T2OUT_7") (pintype "output"))
    )
    (net (code "87") (name "unconnected-(IC4-(ADC2)PA2-Pad38)") (class "Default")
      (node (ref "IC4") (pin "38") (pinfunction "(ADC2)PA2_38") (pintype "bidirectional"))
    )
    (net (code "88") (name "unconnected-(IC4-(INT0)PD2-Pad16)") (class "Default")
      (node (ref "IC4") (pin "16") (pinfunction "(INT0)PD2_16") (pintype "bidirectional"))
    )
    (net (code "89") (name "unconnected-(IC4-(OC2)PD7-Pad21)") (class "Default")
      (node (ref "IC4") (pin "21") (pinfunction "(OC2)PD7_21") (pintype "bidirectional"))
    )
    (net (code "90") (name "unconnected-(IC4-(SCL)PC0-Pad22)") (class "Default")
      (node (ref "IC4") (pin "22") (pinfunction "(SCL)PC0_22") (pintype "bidirectional"))
    )
    (net (code "91") (name "unconnected-(IC4-(SDA)PC1-Pad23)") (class "Default")
      (node (ref "IC4") (pin "23") (pinfunction "(SDA)PC1_23") (pintype "bidirectional"))
    )
    (net (code "92") (name "unconnected-(IC4-(SS)PB4-Pad5)") (class "Default")
      (node (ref "IC4") (pin "5") (pinfunction "(SS)PB4_5") (pintype "bidirectional"))
    )
    (net (code "93") (name "unconnected-(IC4-(T0{slash}XCK)PB0-Pad1)") (class "Default")
      (node (ref "IC4") (pin "1") (pinfunction "(T0/XCK)PB0_1") (pintype "bidirectional"))
    )
    (net (code "94") (name "unconnected-(IC4-(TDI)PC5-Pad27)") (class "Default")
      (node (ref "IC4") (pin "27") (pinfunction "(TDI)PC5_27") (pintype "bidirectional"))
    )
    (net (code "95") (name "unconnected-(IC4-(TDO)PC4-Pad26)") (class "Default")
      (node (ref "IC4") (pin "26") (pinfunction "(TDO)PC4_26") (pintype "bidirectional"))
    )
    (net (code "96") (name "unconnected-(IC4-(TMS)PC3-Pad25)") (class "Default")
      (node (ref "IC4") (pin "25") (pinfunction "(TMS)PC3_25") (pintype "bidirectional"))
    )
    (net (code "97") (name "unconnected-(IC4-(TOSC1)PC6-Pad28)") (class "Default")
      (node (ref "IC4") (pin "28") (pinfunction "(TOSC1)PC6_28") (pintype "bidirectional"))
    )
    (net (code "98") (name "unconnected-(SV1-Pad3)") (class "Default")
      (node (ref "SV1") (pin "3") (pinfunction "3_3") (pintype "passive"))
    )
    (net (code "99") (name "unconnected-(X1-Pad4)") (class "Default")
      (node (ref "X1") (pin "4") (pinfunction "4_4") (pintype "passive"))
    )
    (net (code "100") (name "unconnected-(X1-Pad6)") (class "Default")
      (node (ref "X1") (pin "6") (pinfunction "6_6") (pintype "passive"))
    )
    (net (code "101") (name "unconnected-(X1-Pad7)") (class "Default")
      (node (ref "X1") (pin "7") (pinfunction "7_7") (pintype "passive"))
    )
    (net (code "102") (name "unconnected-(X1-Pad8)") (class "Default")
      (node (ref "X1") (pin "8") (pinfunction "8_8") (pintype "passive"))
    )
  )
)
